# schematic.net
KiCad netlist of a schematic drawn in EAGLE
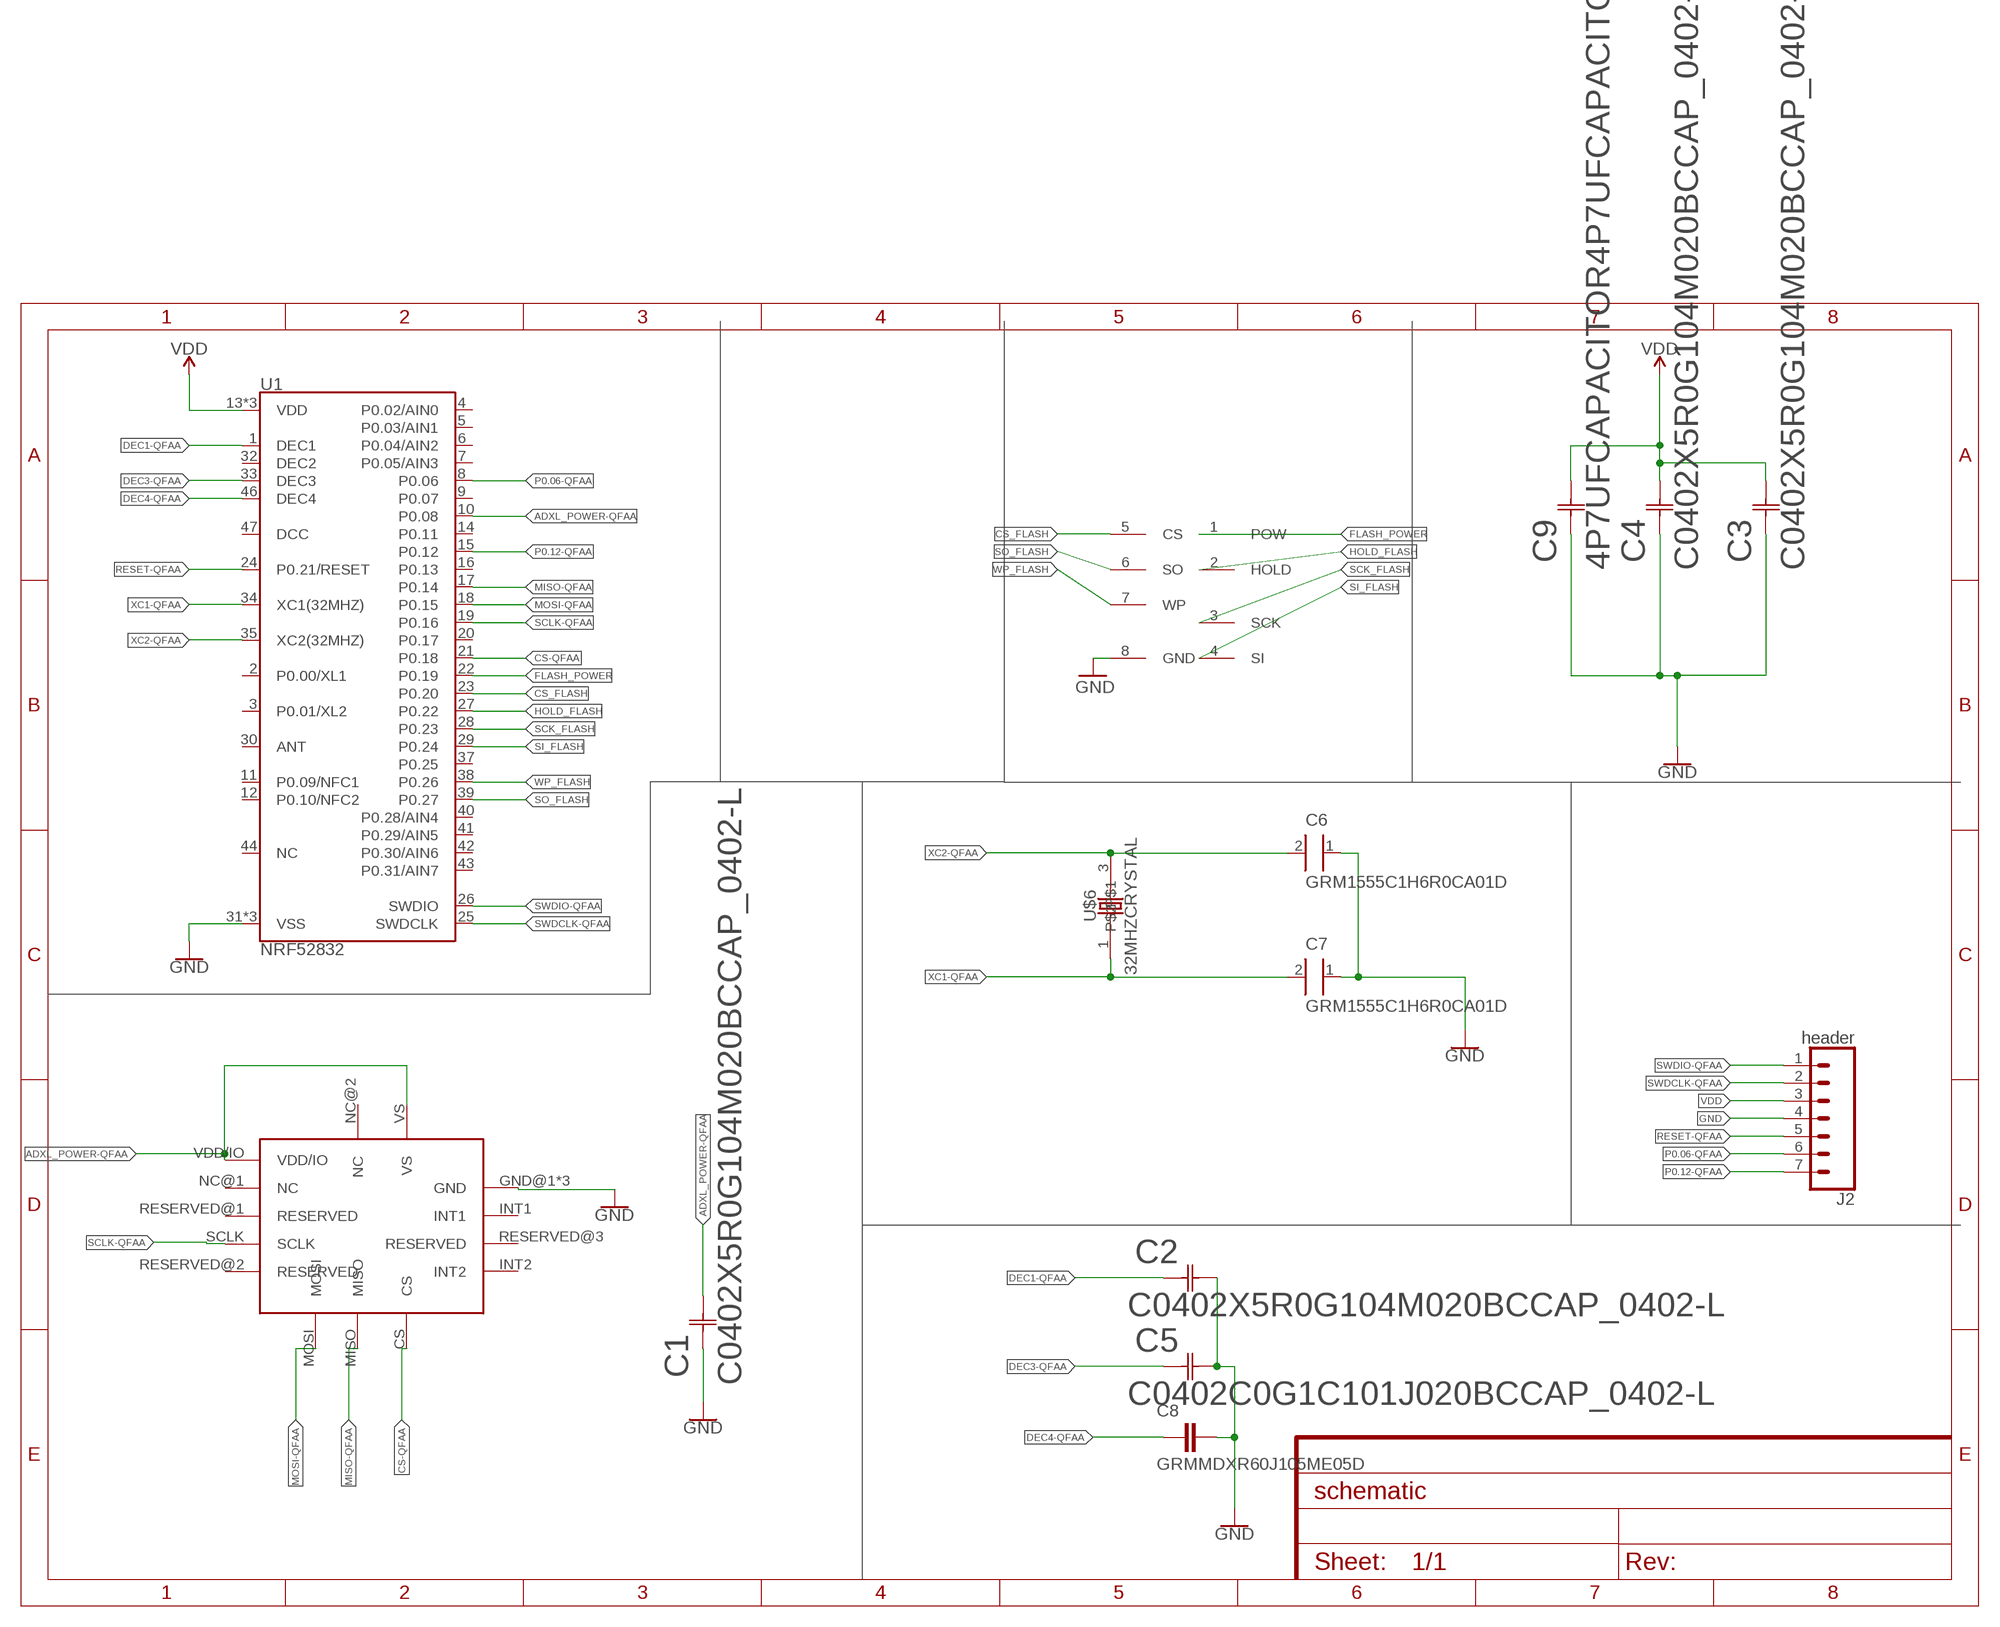
[diagram p0: schematic, sheet 1]

(export (version "E")
  (design (tool "Eeschema 10.0.6"))
  (components
    (comp (ref "C1")
      (value "C0402X5R0G104M020BCCAP_0402-L")
      (footprint "eagle-import:CAP_0402-L")
      (fields (field (name "MANUFACTURER_PART_NUMBER") "C0402C0G1C101J020BC"))
      (libsource (lib "eagle-import") (part "C0402X5R0G104M020BCCAP_0402-L"))
    )
    (comp (ref "C2")
      (value "C0402X5R0G104M020BCCAP_0402-L")
      (footprint "eagle-import:CAP_0402-L")
      (fields (field (name "MANUFACTURER_PART_NUMBER") "C0402C0G1C101J020BC"))
      (libsource (lib "eagle-import") (part "C0402X5R0G104M020BCCAP_0402-L"))
    )
    (comp (ref "C3")
      (value "C0402X5R0G104M020BCCAP_0402-L")
      (footprint "eagle-import:CAP_0402-L")
      (fields (field (name "MANUFACTURER_PART_NUMBER") "C0402C0G1C101J020BC"))
      (libsource (lib "eagle-import") (part "C0402X5R0G104M020BCCAP_0402-L"))
    )
    (comp (ref "C4")
      (value "C0402X5R0G104M020BCCAP_0402-L")
      (footprint "eagle-import:CAP_0402-L")
      (fields (field (name "MANUFACTURER_PART_NUMBER") "C0402C0G1C101J020BC"))
      (libsource (lib "eagle-import") (part "C0402X5R0G104M020BCCAP_0402-L"))
    )
    (comp (ref "C5")
      (value "C0402C0G1C101J020BCCAP_0402-L")
      (footprint "eagle-import:CAP_0402-L")
      (fields (field (name "MANUFACTURER_PART_NUMBER") "C0402C0G1C101J020BC"))
      (libsource (lib "eagle-import") (part "C0402C0G1C101J020BCCAP_0402-L"))
    )
    (comp (ref "C6")
      (value "GRM1555C1H6R0CA01D")
      (footprint "eagle-import:CAPC1005X55N")
      (fields (field (name "DIGI-KEY_PART_NUMBER") "490-8222-1-ND") (field (name "MF") "Murata"))
      (libsource (lib "eagle-import") (part "GRM1555C1H6R0CA01D"))
    )
    (comp (ref "C7")
      (value "GRM1555C1H6R0CA01D")
      (footprint "eagle-import:CAPC1005X55N")
      (fields (field (name "DIGI-KEY_PART_NUMBER") "490-8222-1-ND") (field (name "MF") "Murata"))
      (libsource (lib "eagle-import") (part "GRM1555C1H6R0CA01D"))
    )
    (comp (ref "C8")
      (value "GRMMDXR60J105ME05D")
      (footprint "eagle-import:CAPC0502X28N")
      (fields (field (name "DIGI-KEY_PART_NUMBER") "490-13424-1-ND") (field (name "MF") "Murata"))
      (libsource (lib "eagle-import") (part "GRMMDXR60J105ME05D"))
    )
    (comp (ref "C9")
      (value "4P7UFCAPACITOR4P7UFCAPACITOR")
      (footprint "eagle-import:4P7UFCAPACITOR")
      (fields (field (name "MANUFACTURER_PART_NUMBER") "C0816X5R0J475M050AC"))
      (libsource (lib "eagle-import") (part "4P7UFCAPACITOR4P7UFCAPACITOR"))
    )
    (comp (ref "J2")
      (value "header")
      (footprint "eagle-import:1X07")
      (libsource (lib "eagle-import") (part "CONN_07"))
    )
    (comp (ref "U$1")
      (value "ADXL362")
      (footprint "eagle-import:TFLGA-16_3.3MMX3.1MM")
      (libsource (lib "eagle-import") (part "ADXL362"))
    )
    (comp (ref "U$3")
      (value "AT25SF161-UUD-T")
      (footprint "eagle-import:AT25SF161-UUD-T")
      (libsource (lib "eagle-import") (part "AT25SF161-UUD-T"))
    )
    (comp (ref "U$6")
      (value "32MHZCRYSTAL")
      (footprint "eagle-import:32MHZCRYSTAL")
      (libsource (lib "eagle-import") (part "32MHZCRYSTAL"))
    )
    (comp (ref "U1")
      (value "NRF52832")
      (footprint "eagle-import:QFN48-6X6MM")
      (libsource (lib "eagle-import") (part "NRF52832"))
    )
  )
  (nets
    (net (code "1") (name "ADXL_POWER-QFAA") (class "Default")
      (node (ref "C1") (pin "2") (pinfunction "22_2") (pintype "passive"))
      (node (ref "U$1") (pin "VDD/IO") (pinfunction "VDD/IO_VDD/IO") (pintype "bidirectional"))
      (node (ref "U$1") (pin "VS") (pinfunction "VS_VS") (pintype "bidirectional"))
      (node (ref "U1") (pin "10") (pinfunction "P0.08_10") (pintype "bidirectional"))
    )
    (net (code "2") (name "CS-QFAA") (class "Default")
      (node (ref "U$1") (pin "CS") (pinfunction "CS_CS") (pintype "bidirectional"))
      (node (ref "U1") (pin "21") (pinfunction "P0.18_21") (pintype "bidirectional"))
    )
    (net (code "3") (name "CS_FLASH") (class "Default")
      (node (ref "U$3") (pin "5") (pinfunction "CS_5") (pintype "input"))
      (node (ref "U1") (pin "23") (pinfunction "P0.20_23") (pintype "bidirectional"))
    )
    (net (code "4") (name "DEC1-QFAA") (class "Default")
      (node (ref "C2") (pin "1") (pinfunction "11_1") (pintype "passive"))
      (node (ref "U1") (pin "1") (pinfunction "DEC1_1") (pintype "bidirectional"))
    )
    (net (code "5") (name "DEC3-QFAA") (class "Default")
      (node (ref "C5") (pin "1") (pinfunction "11_1") (pintype "passive"))
      (node (ref "U1") (pin "33") (pinfunction "DEC3_33") (pintype "bidirectional"))
    )
    (net (code "6") (name "DEC4-QFAA") (class "Default")
      (node (ref "C8") (pin "1") (pinfunction "1_1") (pintype "passive"))
      (node (ref "U1") (pin "46") (pinfunction "DEC4_46") (pintype "bidirectional"))
    )
    (net (code "7") (name "FLASH_POWER") (class "Default")
      (node (ref "U$3") (pin "1") (pinfunction "POW_1") (pintype "input"))
      (node (ref "U1") (pin "22") (pinfunction "P0.19_22") (pintype "bidirectional"))
    )
    (net (code "8") (name "GND") (class "Default")
      (node (ref "C1") (pin "1") (pinfunction "11_1") (pintype "passive"))
      (node (ref "C2") (pin "2") (pinfunction "22_2") (pintype "passive"))
      (node (ref "C3") (pin "1") (pinfunction "11_1") (pintype "passive"))
      (node (ref "C4") (pin "1") (pinfunction "11_1") (pintype "passive"))
      (node (ref "C5") (pin "2") (pinfunction "22_2") (pintype "passive"))
      (node (ref "C6") (pin "1") (pinfunction "1_1") (pintype "passive"))
      (node (ref "C7") (pin "1") (pinfunction "1_1") (pintype "passive"))
      (node (ref "C8") (pin "2") (pinfunction "2_2") (pintype "passive"))
      (node (ref "C9") (pin "1") (pinfunction "11_1") (pintype "passive"))
      (node (ref "J2") (pin "4") (pinfunction "4_4") (pintype "passive"))
      (node (ref "U$1") (pin "GND@1") (pinfunction "GND_GND@1") (pintype "bidirectional"))
      (node (ref "U$1") (pin "GND@2") (pinfunction "GND_GND@2") (pintype "bidirectional"))
      (node (ref "U$1") (pin "GND@3") (pinfunction "GND_GND@3") (pintype "bidirectional"))
      (node (ref "U$3") (pin "8") (pinfunction "GND_8") (pintype "power_in"))
      (node (ref "U1") (pin "31") (pinfunction "VSS_31") (pintype "bidirectional"))
      (node (ref "U1") (pin "45") (pinfunction "VSS_45") (pintype "bidirectional"))
      (node (ref "U1") (pin "EP") (pinfunction "VSS_EP") (pintype "bidirectional"))
    )
    (net (code "9") (name "HOLD_FLASH") (class "Default")
      (node (ref "U$3") (pin "2") (pinfunction "HOLD_2") (pintype "bidirectional"))
      (node (ref "U1") (pin "27") (pinfunction "P0.22_27") (pintype "bidirectional"))
    )
    (net (code "10") (name "MISO-QFAA") (class "Default")
      (node (ref "U$1") (pin "MISO") (pinfunction "MISO_MISO") (pintype "bidirectional"))
      (node (ref "U1") (pin "17") (pinfunction "P0.14_17") (pintype "bidirectional"))
    )
    (net (code "11") (name "MOSI-QFAA") (class "Default")
      (node (ref "U$1") (pin "MOSI") (pinfunction "MOSI_MOSI") (pintype "bidirectional"))
      (node (ref "U1") (pin "18") (pinfunction "P0.15_18") (pintype "bidirectional"))
    )
    (net (code "12") (name "P0.06-QFAA") (class "Default")
      (node (ref "J2") (pin "6") (pinfunction "6_6") (pintype "passive"))
      (node (ref "U1") (pin "8") (pinfunction "P0.06_8") (pintype "bidirectional"))
    )
    (net (code "13") (name "P0.12-QFAA") (class "Default")
      (node (ref "J2") (pin "7") (pinfunction "7_7") (pintype "passive"))
      (node (ref "U1") (pin "15") (pinfunction "P0.12_15") (pintype "bidirectional"))
    )
    (net (code "14") (name "RESET-QFAA") (class "Default")
      (node (ref "J2") (pin "5") (pinfunction "5_5") (pintype "passive"))
      (node (ref "U1") (pin "24") (pinfunction "P0.21/RESET_24") (pintype "bidirectional"))
    )
    (net (code "15") (name "SCK_FLASH") (class "Default")
      (node (ref "U$3") (pin "3") (pinfunction "SCK_3") (pintype "input"))
      (node (ref "U1") (pin "28") (pinfunction "P0.23_28") (pintype "bidirectional"))
    )
    (net (code "16") (name "SCLK-QFAA") (class "Default")
      (node (ref "U$1") (pin "SCLK") (pinfunction "SCLK_SCLK") (pintype "bidirectional"))
      (node (ref "U1") (pin "19") (pinfunction "P0.16_19") (pintype "bidirectional"))
    )
    (net (code "17") (name "SI_FLASH") (class "Default")
      (node (ref "U$3") (pin "4") (pinfunction "SI_4") (pintype "bidirectional"))
      (node (ref "U1") (pin "29") (pinfunction "P0.24_29") (pintype "bidirectional"))
    )
    (net (code "18") (name "SO_FLASH") (class "Default")
      (node (ref "U$3") (pin "6") (pinfunction "SO_6") (pintype "bidirectional"))
      (node (ref "U1") (pin "39") (pinfunction "P0.27_39") (pintype "bidirectional"))
    )
    (net (code "19") (name "SWDCLK-QFAA") (class "Default")
      (node (ref "J2") (pin "2") (pinfunction "2_2") (pintype "passive"))
      (node (ref "U1") (pin "25") (pinfunction "SWDCLK_25") (pintype "bidirectional"))
    )
    (net (code "20") (name "SWDIO-QFAA") (class "Default")
      (node (ref "J2") (pin "1") (pinfunction "1_1") (pintype "passive"))
      (node (ref "U1") (pin "26") (pinfunction "SWDIO_26") (pintype "bidirectional"))
    )
    (net (code "21") (name "VDD") (class "Default")
      (node (ref "C3") (pin "2") (pinfunction "22_2") (pintype "passive"))
      (node (ref "C4") (pin "2") (pinfunction "22_2") (pintype "passive"))
      (node (ref "C9") (pin "2") (pinfunction "22_2") (pintype "passive"))
      (node (ref "J2") (pin "3") (pinfunction "3_3") (pintype "passive"))
      (node (ref "U1") (pin "13") (pinfunction "VDD_13") (pintype "bidirectional"))
      (node (ref "U1") (pin "36") (pinfunction "VDD_36") (pintype "bidirectional"))
      (node (ref "U1") (pin "48") (pinfunction "VDD_48") (pintype "bidirectional"))
    )
    (net (code "22") (name "WP_FLASH") (class "Default")
      (node (ref "U$3") (pin "7") (pinfunction "WP_7") (pintype "bidirectional"))
      (node (ref "U1") (pin "38") (pinfunction "P0.26_38") (pintype "bidirectional"))
    )
    (net (code "23") (name "XC1-QFAA") (class "Default")
      (node (ref "C7") (pin "2") (pinfunction "2_2") (pintype "passive"))
      (node (ref "U$6") (pin "1") (pinfunction "P$1_1") (pintype "bidirectional"))
      (node (ref "U1") (pin "34") (pinfunction "XC1(32MHZ)_34") (pintype "bidirectional"))
    )
    (net (code "24") (name "XC2-QFAA") (class "Default")
      (node (ref "C6") (pin "2") (pinfunction "2_2") (pintype "passive"))
      (node (ref "U$6") (pin "3") (pinfunction "P$2_3") (pintype "bidirectional"))
      (node (ref "U1") (pin "35") (pinfunction "XC2(32MHZ)_35") (pintype "bidirectional"))
    )
    (net (code "25") (name "unconnected-(U$1-NC-PadNC@1)") (class "Default")
      (node (ref "U$1") (pin "NC@1") (pinfunction "NC_NC@1") (pintype "bidirectional"))
    )
    (net (code "26") (name "unconnected-(U$1-NC-PadNC@2)") (class "Default")
      (node (ref "U$1") (pin "NC@2") (pinfunction "NC_NC@2") (pintype "bidirectional"))
    )
    (net (code "27") (name "unconnected-(U$1-PadINT1)") (class "Default")
      (node (ref "U$1") (pin "INT1") (pinfunction "INT1_INT1") (pintype "bidirectional"))
    )
    (net (code "28") (name "unconnected-(U$1-PadINT2)") (class "Default")
      (node (ref "U$1") (pin "INT2") (pinfunction "INT2_INT2") (pintype "bidirectional"))
    )
    (net (code "29") (name "unconnected-(U$1-RESERVED-PadRESERVED@1)") (class "Default")
      (node (ref "U$1") (pin "RESERVED@1") (pinfunction "RESERVED_RESERVED@1") (pintype "bidirectional"))
    )
    (net (code "30") (name "unconnected-(U$1-RESERVED-PadRESERVED@2)") (class "Default")
      (node (ref "U$1") (pin "RESERVED@2") (pinfunction "RESERVED_RESERVED@2") (pintype "bidirectional"))
    )
    (net (code "31") (name "unconnected-(U$1-RESERVED-PadRESERVED@3)") (class "Default")
      (node (ref "U$1") (pin "RESERVED@3") (pinfunction "RESERVED_RESERVED@3") (pintype "bidirectional"))
    )
    (net (code "32") (name "unconnected-(U1-ANT-Pad30)") (class "Default")
      (node (ref "U1") (pin "30") (pinfunction "ANT_30") (pintype "bidirectional"))
    )
    (net (code "33") (name "unconnected-(U1-DCC-Pad47)") (class "Default")
      (node (ref "U1") (pin "47") (pinfunction "DCC_47") (pintype "bidirectional"))
    )
    (net (code "34") (name "unconnected-(U1-DEC2-Pad32)") (class "Default")
      (node (ref "U1") (pin "32") (pinfunction "DEC2_32") (pintype "bidirectional"))
    )
    (net (code "35") (name "unconnected-(U1-NC-Pad44)") (class "Default")
      (node (ref "U1") (pin "44") (pinfunction "NC_44") (pintype "bidirectional"))
    )
    (net (code "36") (name "unconnected-(U1-P0.00{slash}XL1-Pad2)") (class "Default")
      (node (ref "U1") (pin "2") (pinfunction "P0.00/XL1_2") (pintype "bidirectional"))
    )
    (net (code "37") (name "unconnected-(U1-P0.01{slash}XL2-Pad3)") (class "Default")
      (node (ref "U1") (pin "3") (pinfunction "P0.01/XL2_3") (pintype "bidirectional"))
    )
    (net (code "38") (name "unconnected-(U1-P0.02{slash}AIN0-Pad4)") (class "Default")
      (node (ref "U1") (pin "4") (pinfunction "P0.02/AIN0_4") (pintype "bidirectional"))
    )
    (net (code "39") (name "unconnected-(U1-P0.03{slash}AIN1-Pad5)") (class "Default")
      (node (ref "U1") (pin "5") (pinfunction "P0.03/AIN1_5") (pintype "bidirectional"))
    )
    (net (code "40") (name "unconnected-(U1-P0.04{slash}AIN2-Pad6)") (class "Default")
      (node (ref "U1") (pin "6") (pinfunction "P0.04/AIN2_6") (pintype "bidirectional"))
    )
    (net (code "41") (name "unconnected-(U1-P0.05{slash}AIN3-Pad7)") (class "Default")
      (node (ref "U1") (pin "7") (pinfunction "P0.05/AIN3_7") (pintype "bidirectional"))
    )
    (net (code "42") (name "unconnected-(U1-P0.07-Pad9)") (class "Default")
      (node (ref "U1") (pin "9") (pinfunction "P0.07_9") (pintype "bidirectional"))
    )
    (net (code "43") (name "unconnected-(U1-P0.09{slash}NFC1-Pad11)") (class "Default")
      (node (ref "U1") (pin "11") (pinfunction "P0.09/NFC1_11") (pintype "bidirectional"))
    )
    (net (code "44") (name "unconnected-(U1-P0.10{slash}NFC2-Pad12)") (class "Default")
      (node (ref "U1") (pin "12") (pinfunction "P0.10/NFC2_12") (pintype "bidirectional"))
    )
    (net (code "45") (name "unconnected-(U1-P0.11-Pad14)") (class "Default")
      (node (ref "U1") (pin "14") (pinfunction "P0.11_14") (pintype "bidirectional"))
    )
    (net (code "46") (name "unconnected-(U1-P0.13-Pad16)") (class "Default")
      (node (ref "U1") (pin "16") (pinfunction "P0.13_16") (pintype "bidirectional"))
    )
    (net (code "47") (name "unconnected-(U1-P0.17-Pad20)") (class "Default")
      (node (ref "U1") (pin "20") (pinfunction "P0.17_20") (pintype "bidirectional"))
    )
    (net (code "48") (name "unconnected-(U1-P0.25-Pad37)") (class "Default")
      (node (ref "U1") (pin "37") (pinfunction "P0.25_37") (pintype "bidirectional"))
    )
    (net (code "49") (name "unconnected-(U1-P0.28{slash}AIN4-Pad40)") (class "Default")
      (node (ref "U1") (pin "40") (pinfunction "P0.28/AIN4_40") (pintype "bidirectional"))
    )
    (net (code "50") (name "unconnected-(U1-P0.29{slash}AIN5-Pad41)") (class "Default")
      (node (ref "U1") (pin "41") (pinfunction "P0.29/AIN5_41") (pintype "bidirectional"))
    )
    (net (code "51") (name "unconnected-(U1-P0.30{slash}AIN6-Pad42)") (class "Default")
      (node (ref "U1") (pin "42") (pinfunction "P0.30/AIN6_42") (pintype "bidirectional"))
    )
    (net (code "52") (name "unconnected-(U1-P0.31{slash}AIN7-Pad43)") (class "Default")
      (node (ref "U1") (pin "43") (pinfunction "P0.31/AIN7_43") (pintype "bidirectional"))
    )
  )
)
